# DigitalConverter.net
KiCad netlist of a schematic drawn in Altium Designer
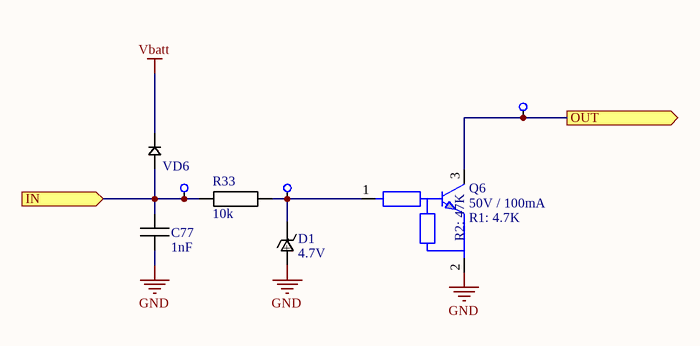
[diagram p0: DigitalConverter.SchDoc]

(export (version "E")
  (design (tool "Eeschema 10.0.6"))
  (components
    (comp (ref "C77")
      (value "1nF")
      (footprint "SMD 0603")
      (description "CC0603KRX7R9BB102")
      (libsource (lib "Maks_lib") (part "Capasitor"))
    )
    (comp (ref "D1")
      (value "4.7V")
      (footprint "SOD323")
      (description "BZX384-C4V7.115")
      (libsource (lib "Maks_lib") (part "Zener"))
    )
    (comp (ref "Q6")
      (value "50V / 100mA")
      (footprint "SOT23")
      (description "NPN")
      (fields (field (name "R1") "4.7K") (field (name "R2") "47K"))
      (libsource (lib "Maks_lib") (part "PDTC143ZT"))
    )
    (comp (ref "R33")
      (value "10k")
      (footprint "SMD 0603")
      (description "RC0603FR-0710KL")
      (libsource (lib "Maks_lib") (part "Resistor"))
    )
    (comp (ref "TP50")
      (value "TestPoint")
      (footprint "TESTPOINT")
      (description "testPoint")
      (libsource (lib "Maks_lib") (part "TestPoint"))
    )
    (comp (ref "TP51")
      (value "TestPoint")
      (footprint "TESTPOINT")
      (description "testPoint")
      (libsource (lib "Maks_lib") (part "TestPoint"))
    )
    (comp (ref "TP52")
      (value "TestPoint")
      (footprint "TESTPOINT")
      (description "testPoint")
      (libsource (lib "Maks_lib") (part "TestPoint"))
    )
    (comp (ref "VD6")
      (value "Diode")
      (footprint "SOD323")
      (description "PMEG2020EJ.115")
      (libsource (lib "Maks_lib") (part "Diode"))
    )
  )
  (nets
    (net (code "1") (name "/IN") (class "Default")
      (node (ref "C77") (pin "2") (pinfunction "2_2") (pintype "passive"))
      (node (ref "R33") (pin "1") (pinfunction "1_1") (pintype "passive"))
      (node (ref "TP50") (pin "0") (pinfunction "0_0") (pintype "passive"))
      (node (ref "VD6") (pin "0") (pinfunction "0_0") (pintype "passive"))
    )
    (net (code "2") (name "/OUT") (class "Default")
      (node (ref "Q6") (pin "3") (pinfunction "C_3") (pintype "passive"))
      (node (ref "TP52") (pin "0") (pinfunction "0_0") (pintype "passive"))
    )
    (net (code "3") (name "GND") (class "Default")
      (node (ref "C77") (pin "1") (pinfunction "1_1") (pintype "passive"))
      (node (ref "D1") (pin "-") (pinfunction "-_-") (pintype "passive"))
      (node (ref "Q6") (pin "2") (pinfunction "E_2") (pintype "passive"))
    )
    (net (code "4") (name "Net-(Q6-B)") (class "Default")
      (node (ref "D1") (pin "+") (pinfunction "+_+") (pintype "passive"))
      (node (ref "Q6") (pin "1") (pinfunction "B_1") (pintype "passive"))
      (node (ref "R33") (pin "2") (pinfunction "2_2") (pintype "passive"))
      (node (ref "TP51") (pin "0") (pinfunction "0_0") (pintype "passive"))
    )
    (net (code "5") (name "Vbatt") (class "Default")
      (node (ref "VD6") (pin "1") (pinfunction "1_1") (pintype "passive"))
    )
  )
)
